# FTPLUS_v1_1.net
KiCad netlist of a schematic drawn in EasyEDA
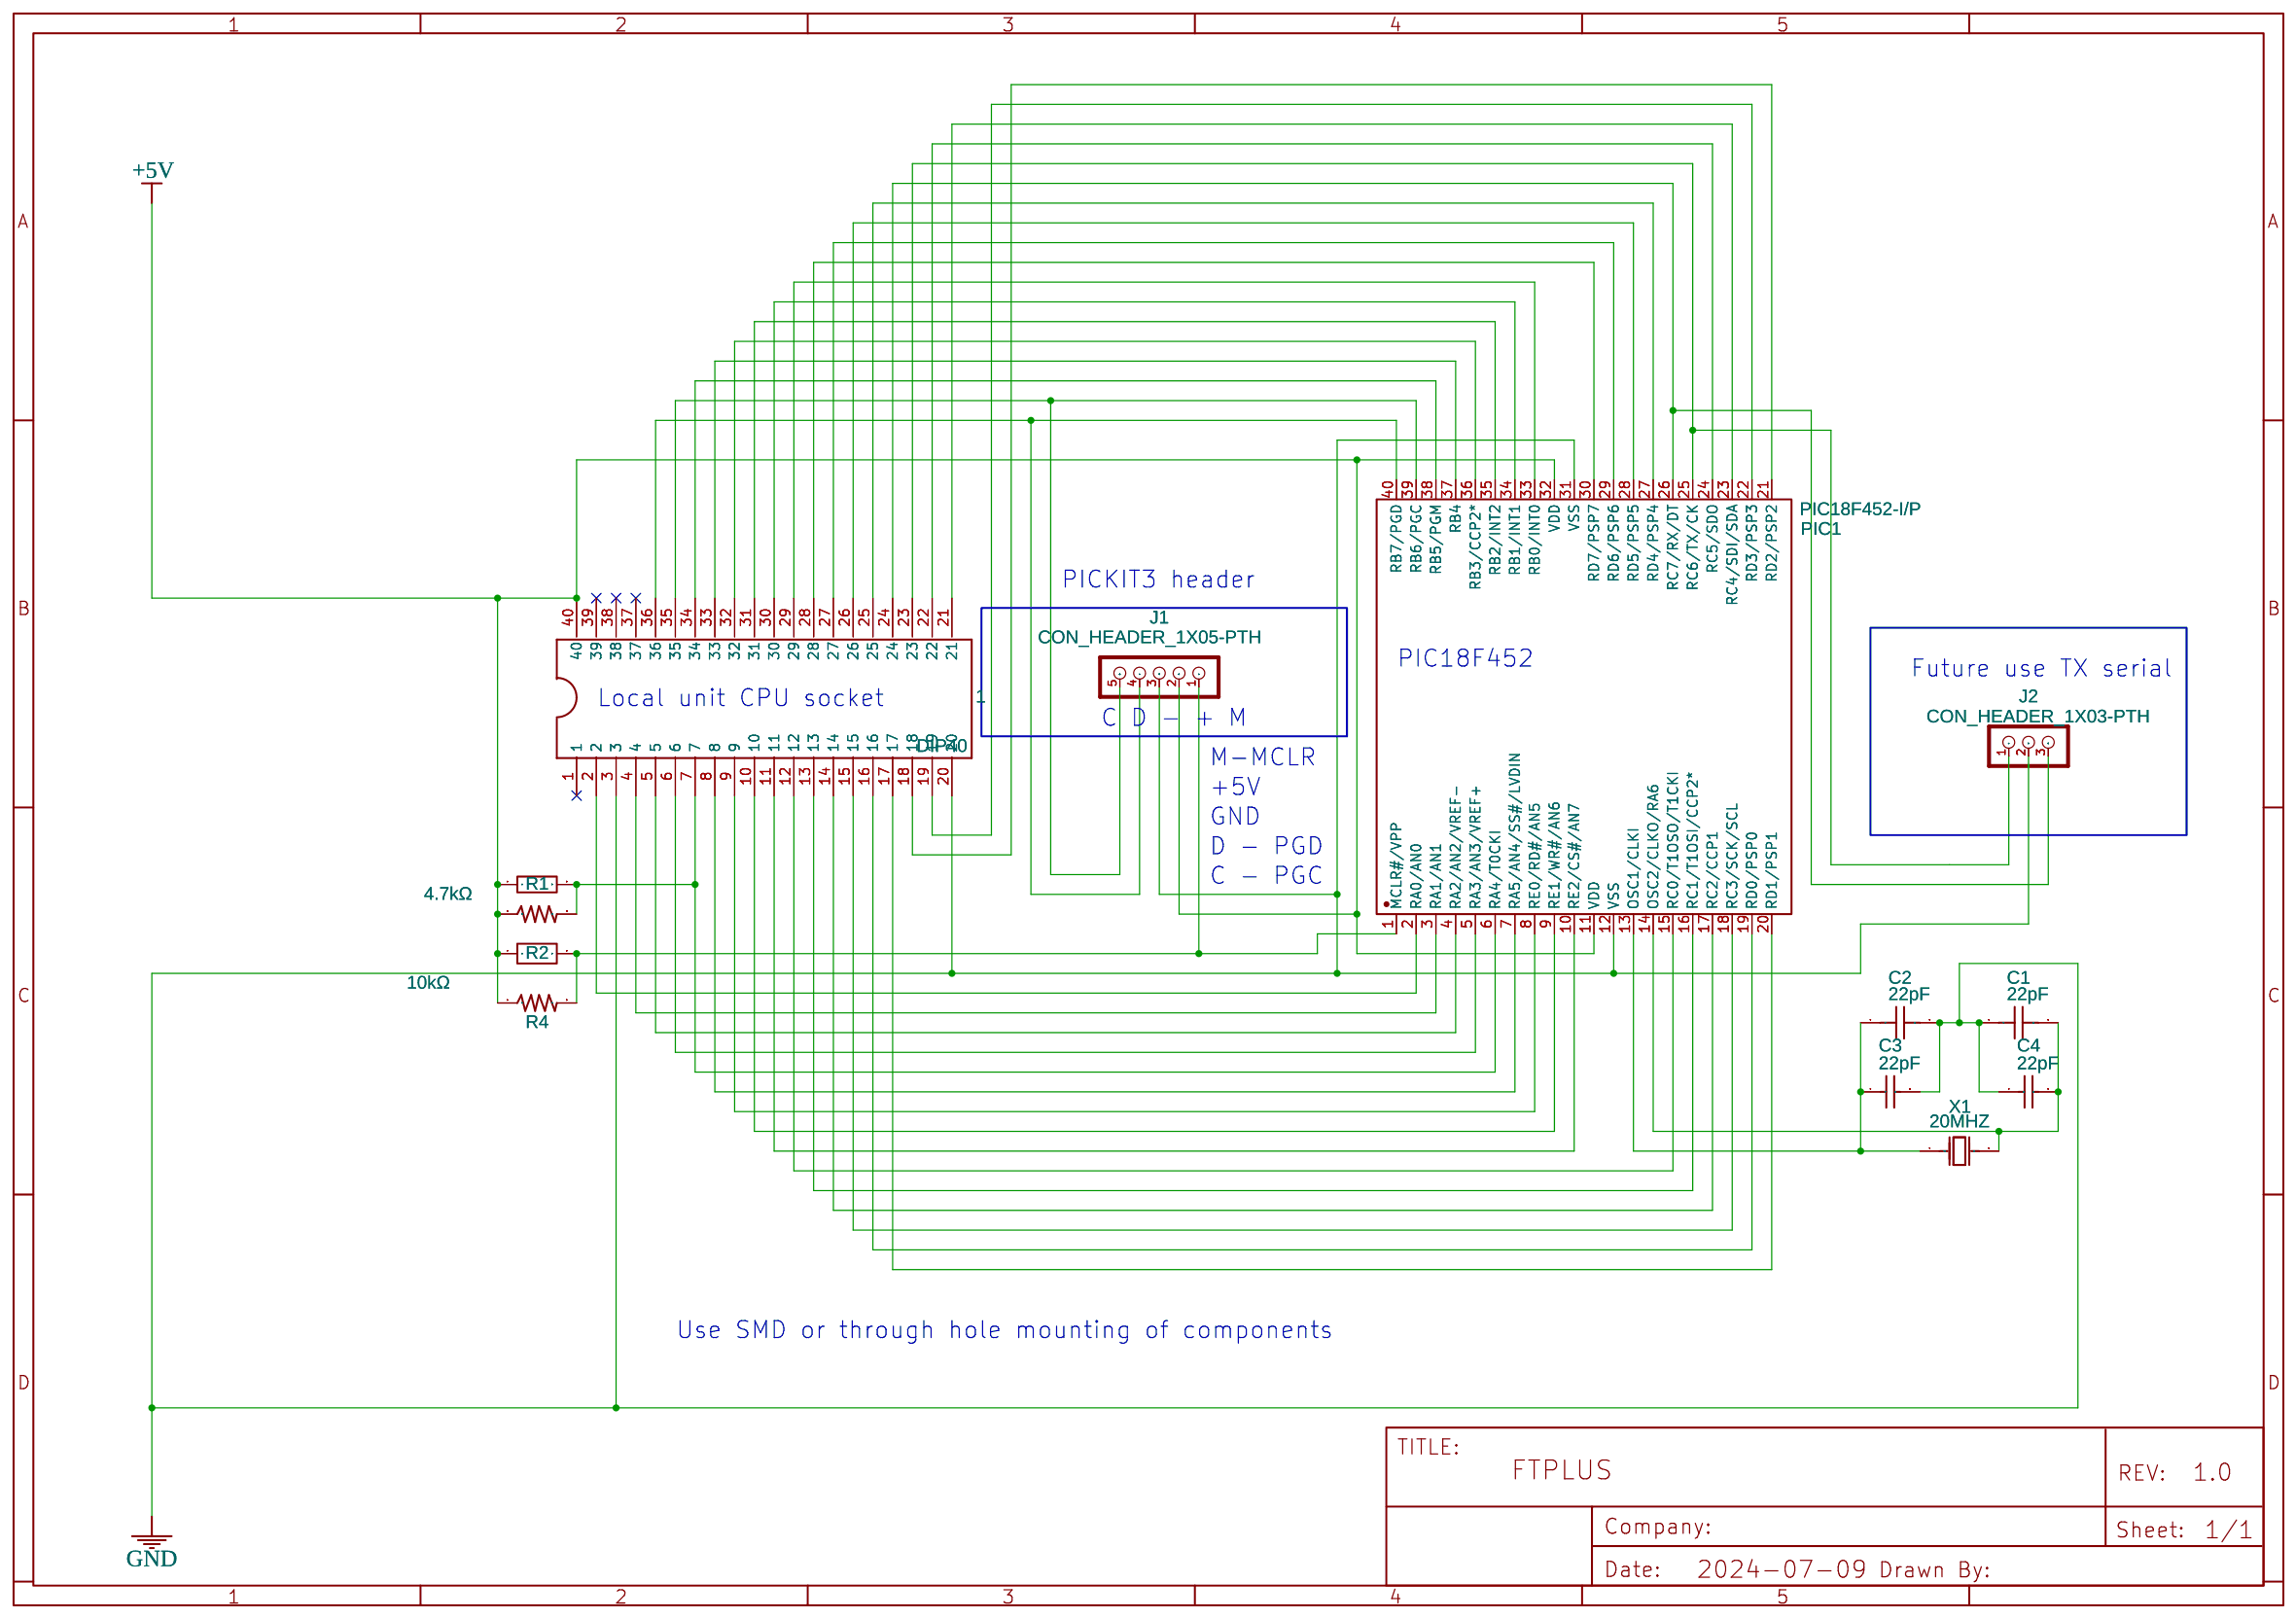
[diagram p0: schematic sheet]

(export (version "E")
  (design (tool "Eeschema 10.0.6"))
  (components
    (comp (ref "1") (value "DIP40") (libsource (lib "") (part "DIP40")))
    (comp (ref "C1")
      (value "22pF")
      (fields
        (field (name "Manufacturer Part") "CSA0603C0G220J500JT")
        (field (name "Manufacturer") "HRE(芯声)")
      )
      (libsource (lib "") (part "CSA0603C0G220J500JT"))
    )
    (comp (ref "C2")
      (value "22pF")
      (fields
        (field (name "Manufacturer Part") "CSA0603C0G220J500JT")
        (field (name "Manufacturer") "HRE(芯声)")
      )
      (libsource (lib "") (part "CSA0603C0G220J500JT"))
    )
    (comp (ref "C3")
      (value "22pF")
      (fields (field (name "Manufacturer Part") "22K-50V") (field (name "Manufacturer") "LCSC"))
      (libsource (lib "") (part "22pF"))
    )
    (comp (ref "C4")
      (value "22pF")
      (fields (field (name "Manufacturer Part") "22K-50V") (field (name "Manufacturer") "LCSC"))
      (libsource (lib "") (part "22pF"))
    )
    (comp (ref "J1") (value "CON_HEADER_1X05-PTH") (libsource (lib "") (part "CON_HEADER_1X05-PTH")))
    (comp (ref "J2") (value "CON_HEADER_1X03-PTH") (libsource (lib "") (part "CON_HEADER_1X03-PTH")))
    (comp (ref "PIC1")
      (value "PIC18F452-I/P")
      (fields (field (name "Manufacturer") "MICROCHIP(美国微芯)"))
      (libsource (lib "") (part "PIC18F452-I/P"))
    )
    (comp (ref "R1")
      (value "4.7kΩ")
      (fields
        (field (name "Manufacturer Part") "0603WAF4701T5E")
        (field (name "Manufacturer") "UNI-ROYAL(厚声)")
      )
      (libsource (lib "") (part "0603WAF4701T5E"))
    )
    (comp (ref "R2")
      (value "10kΩ")
      (fields
        (field (name "Manufacturer Part") "TC0325D1002T5F")
        (field (name "Manufacturer") "UNI-ROYAL(厚声)")
      )
      (libsource (lib "") (part "TC0325D1002T5F"))
    )
    (comp (ref "R3") (value "RESISTOR") (libsource (lib "") (part "RESISTOREZ")))
    (comp (ref "R4") (value "RESISTOREZ") (libsource (lib "") (part "RESISTOREZ")))
    (comp (ref "X1")
      (value "20MHZ")
      (fields (field (name "Manufacturer Part") "X49SD20MPB2SC") (field (name "Manufacturer") "EasyEDA"))
      (libsource (lib "") (part "20MHZ"))
    )
  )
  (nets
    (net (code "1") (name "+5V") (class "Default")
      (node (ref "1") (pin "40") (pinfunction "40_40") (pintype "bidirectional"))
      (node (ref "J1") (pin "2") (pinfunction "2_2") (pintype "unspecified"))
      (node (ref "PIC1") (pin "11") (pinfunction "VDD_11") (pintype "unspecified"))
      (node (ref "PIC1") (pin "32") (pinfunction "VDD_32") (pintype "unspecified"))
      (node (ref "R1") (pin "1") (pinfunction "1_1") (pintype "input"))
      (node (ref "R2") (pin "1") (pinfunction "1_1") (pintype "unspecified"))
      (node (ref "R3") (pin "1") (pinfunction "1_1") (pintype "unspecified"))
      (node (ref "R4") (pin "1") (pinfunction "1_1") (pintype "unspecified"))
    )
    (net (code "2") (name "GND") (class "Default")
      (node (ref "1") (pin "20") (pinfunction "20_20") (pintype "bidirectional"))
      (node (ref "1") (pin "3") (pinfunction "3_3") (pintype "bidirectional"))
      (node (ref "C1") (pin "1") (pinfunction "1_1") (pintype "unspecified"))
      (node (ref "C2") (pin "2") (pinfunction "2_2") (pintype "unspecified"))
      (node (ref "C3") (pin "2") (pinfunction "2_2") (pintype "input"))
      (node (ref "C4") (pin "1") (pinfunction "1_1") (pintype "input"))
      (node (ref "J1") (pin "3") (pinfunction "3_3") (pintype "unspecified"))
      (node (ref "J2") (pin "2") (pinfunction "2_2") (pintype "unspecified"))
      (node (ref "PIC1") (pin "12") (pinfunction "VSS_12") (pintype "unspecified"))
      (node (ref "PIC1") (pin "31") (pinfunction "VSS_31") (pintype "unspecified"))
    )
    (net (code "3") (name "Net-(PIC1-MCLR#{slash}VPP)") (class "Default")
      (node (ref "J1") (pin "1") (pinfunction "1_1") (pintype "unspecified"))
      (node (ref "PIC1") (pin "1") (pinfunction "MCLR#/VPP_1") (pintype "unspecified"))
      (node (ref "R2") (pin "2") (pinfunction "2_2") (pintype "unspecified"))
      (node (ref "R4") (pin "2") (pinfunction "2_2") (pintype "unspecified"))
    )
    (net (code "4") (name "Net-(PIC1-OSC1{slash}CLKI)") (class "Default")
      (node (ref "C2") (pin "1") (pinfunction "1_1") (pintype "unspecified"))
      (node (ref "C3") (pin "1") (pinfunction "1_1") (pintype "input"))
      (node (ref "PIC1") (pin "13") (pinfunction "OSC1/CLKI_13") (pintype "unspecified"))
      (node (ref "X1") (pin "1") (pinfunction "OSC1_1") (pintype "unspecified"))
    )
    (net (code "5") (name "Net-(PIC1-OSC2{slash}CLKO{slash}RA6)") (class "Default")
      (node (ref "C1") (pin "2") (pinfunction "2_2") (pintype "unspecified"))
      (node (ref "C4") (pin "2") (pinfunction "2_2") (pintype "input"))
      (node (ref "PIC1") (pin "14") (pinfunction "OSC2/CLKO/RA6_14") (pintype "unspecified"))
      (node (ref "X1") (pin "2") (pinfunction "OSC2_2") (pintype "unspecified"))
    )
    (net (code "6") (name "Net-(PIC1-RA0{slash}AN0)") (class "Default")
      (node (ref "1") (pin "2") (pinfunction "2_2") (pintype "bidirectional"))
      (node (ref "PIC1") (pin "2") (pinfunction "RA0/AN0_2") (pintype "unspecified"))
    )
    (net (code "7") (name "Net-(PIC1-RA1{slash}AN1)") (class "Default")
      (node (ref "1") (pin "4") (pinfunction "4_4") (pintype "bidirectional"))
      (node (ref "PIC1") (pin "3") (pinfunction "RA1/AN1_3") (pintype "unspecified"))
    )
    (net (code "8") (name "Net-(PIC1-RA2{slash}AN2{slash}VREF-)") (class "Default")
      (node (ref "1") (pin "5") (pinfunction "5_5") (pintype "bidirectional"))
      (node (ref "PIC1") (pin "4") (pinfunction "RA2/AN2/VREF-_4") (pintype "unspecified"))
    )
    (net (code "9") (name "Net-(PIC1-RA3{slash}AN3{slash}VREF+)") (class "Default")
      (node (ref "1") (pin "6") (pinfunction "6_6") (pintype "bidirectional"))
      (node (ref "PIC1") (pin "5") (pinfunction "RA3/AN3/VREF+_5") (pintype "unspecified"))
    )
    (net (code "10") (name "Net-(PIC1-RA4{slash}T0CKI)") (class "Default")
      (node (ref "1") (pin "7") (pinfunction "7_7") (pintype "bidirectional"))
      (node (ref "PIC1") (pin "6") (pinfunction "RA4/T0CKI_6") (pintype "unspecified"))
      (node (ref "R1") (pin "2") (pinfunction "2_2") (pintype "input"))
      (node (ref "R3") (pin "2") (pinfunction "2_2") (pintype "unspecified"))
    )
    (net (code "11") (name "Net-(PIC1-RA5{slash}AN4{slash}SS#{slash}LVDIN)") (class "Default")
      (node (ref "1") (pin "8") (pinfunction "8_8") (pintype "bidirectional"))
      (node (ref "PIC1") (pin "7") (pinfunction "RA5/AN4/SS#/LVDIN_7") (pintype "unspecified"))
    )
    (net (code "12") (name "Net-(PIC1-RB0{slash}INT0)") (class "Default")
      (node (ref "1") (pin "29") (pinfunction "29_29") (pintype "bidirectional"))
      (node (ref "PIC1") (pin "33") (pinfunction "RB0/INT0_33") (pintype "unspecified"))
    )
    (net (code "13") (name "Net-(PIC1-RB1{slash}INT1)") (class "Default")
      (node (ref "1") (pin "30") (pinfunction "30_30") (pintype "bidirectional"))
      (node (ref "PIC1") (pin "34") (pinfunction "RB1/INT1_34") (pintype "unspecified"))
    )
    (net (code "14") (name "Net-(PIC1-RB2{slash}INT2)") (class "Default")
      (node (ref "1") (pin "31") (pinfunction "31_31") (pintype "bidirectional"))
      (node (ref "PIC1") (pin "35") (pinfunction "RB2/INT2_35") (pintype "unspecified"))
    )
    (net (code "15") (name "Net-(PIC1-RB3{slash}CCP2*)") (class "Default")
      (node (ref "1") (pin "32") (pinfunction "32_32") (pintype "bidirectional"))
      (node (ref "PIC1") (pin "36") (pinfunction "RB3/CCP2*_36") (pintype "unspecified"))
    )
    (net (code "16") (name "Net-(PIC1-RB4)") (class "Default")
      (node (ref "1") (pin "33") (pinfunction "33_33") (pintype "bidirectional"))
      (node (ref "PIC1") (pin "37") (pinfunction "RB4_37") (pintype "unspecified"))
    )
    (net (code "17") (name "Net-(PIC1-RB5{slash}PGM)") (class "Default")
      (node (ref "1") (pin "34") (pinfunction "34_34") (pintype "bidirectional"))
      (node (ref "PIC1") (pin "38") (pinfunction "RB5/PGM_38") (pintype "unspecified"))
    )
    (net (code "18") (name "Net-(PIC1-RB6{slash}PGC)") (class "Default")
      (node (ref "1") (pin "35") (pinfunction "35_35") (pintype "bidirectional"))
      (node (ref "J1") (pin "5") (pinfunction "5_5") (pintype "unspecified"))
      (node (ref "PIC1") (pin "39") (pinfunction "RB6/PGC_39") (pintype "unspecified"))
    )
    (net (code "19") (name "Net-(PIC1-RB7{slash}PGD)") (class "Default")
      (node (ref "1") (pin "36") (pinfunction "36_36") (pintype "bidirectional"))
      (node (ref "J1") (pin "4") (pinfunction "4_4") (pintype "unspecified"))
      (node (ref "PIC1") (pin "40") (pinfunction "RB7/PGD_40") (pintype "unspecified"))
    )
    (net (code "20") (name "Net-(PIC1-RC0{slash}T1OSO{slash}T1CKI)") (class "Default")
      (node (ref "1") (pin "12") (pinfunction "12_12") (pintype "bidirectional"))
      (node (ref "PIC1") (pin "15") (pinfunction "RC0/T1OSO/T1CKI_15") (pintype "unspecified"))
    )
    (net (code "21") (name "Net-(PIC1-RC1{slash}T1OSI{slash}CCP2*)") (class "Default")
      (node (ref "1") (pin "13") (pinfunction "13_13") (pintype "bidirectional"))
      (node (ref "PIC1") (pin "16") (pinfunction "RC1/T1OSI/CCP2*_16") (pintype "unspecified"))
    )
    (net (code "22") (name "Net-(PIC1-RC2{slash}CCP1)") (class "Default")
      (node (ref "1") (pin "14") (pinfunction "14_14") (pintype "bidirectional"))
      (node (ref "PIC1") (pin "17") (pinfunction "RC2/CCP1_17") (pintype "unspecified"))
    )
    (net (code "23") (name "Net-(PIC1-RC3{slash}SCK{slash}SCL)") (class "Default")
      (node (ref "1") (pin "15") (pinfunction "15_15") (pintype "bidirectional"))
      (node (ref "PIC1") (pin "18") (pinfunction "RC3/SCK/SCL_18") (pintype "unspecified"))
    )
    (net (code "24") (name "Net-(PIC1-RC4{slash}SDI{slash}SDA)") (class "Default")
      (node (ref "1") (pin "21") (pinfunction "21_21") (pintype "bidirectional"))
      (node (ref "PIC1") (pin "23") (pinfunction "RC4/SDI/SDA_23") (pintype "unspecified"))
    )
    (net (code "25") (name "Net-(PIC1-RC5{slash}SDO)") (class "Default")
      (node (ref "1") (pin "22") (pinfunction "22_22") (pintype "bidirectional"))
      (node (ref "PIC1") (pin "24") (pinfunction "RC5/SDO_24") (pintype "unspecified"))
    )
    (net (code "26") (name "Net-(PIC1-RC6{slash}TX{slash}CK)") (class "Default")
      (node (ref "1") (pin "23") (pinfunction "23_23") (pintype "bidirectional"))
      (node (ref "J2") (pin "1") (pinfunction "1_1") (pintype "unspecified"))
      (node (ref "PIC1") (pin "25") (pinfunction "RC6/TX/CK_25") (pintype "unspecified"))
    )
    (net (code "27") (name "Net-(PIC1-RC7{slash}RX{slash}DT)") (class "Default")
      (node (ref "1") (pin "24") (pinfunction "24_24") (pintype "bidirectional"))
      (node (ref "J2") (pin "3") (pinfunction "3_3") (pintype "unspecified"))
      (node (ref "PIC1") (pin "26") (pinfunction "RC7/RX/DT_26") (pintype "unspecified"))
    )
    (net (code "28") (name "Net-(PIC1-RD0{slash}PSP0)") (class "Default")
      (node (ref "1") (pin "16") (pinfunction "16_16") (pintype "bidirectional"))
      (node (ref "PIC1") (pin "19") (pinfunction "RD0/PSP0_19") (pintype "unspecified"))
    )
    (net (code "29") (name "Net-(PIC1-RD1{slash}PSP1)") (class "Default")
      (node (ref "1") (pin "17") (pinfunction "17_17") (pintype "bidirectional"))
      (node (ref "PIC1") (pin "20") (pinfunction "RD1/PSP1_20") (pintype "unspecified"))
    )
    (net (code "30") (name "Net-(PIC1-RD2{slash}PSP2)") (class "Default")
      (node (ref "1") (pin "18") (pinfunction "18_18") (pintype "bidirectional"))
      (node (ref "PIC1") (pin "21") (pinfunction "RD2/PSP2_21") (pintype "unspecified"))
    )
    (net (code "31") (name "Net-(PIC1-RD3{slash}PSP3)") (class "Default")
      (node (ref "1") (pin "19") (pinfunction "19_19") (pintype "bidirectional"))
      (node (ref "PIC1") (pin "22") (pinfunction "RD3/PSP3_22") (pintype "unspecified"))
    )
    (net (code "32") (name "Net-(PIC1-RD4{slash}PSP4)") (class "Default")
      (node (ref "1") (pin "25") (pinfunction "25_25") (pintype "bidirectional"))
      (node (ref "PIC1") (pin "27") (pinfunction "RD4/PSP4_27") (pintype "unspecified"))
    )
    (net (code "33") (name "Net-(PIC1-RD5{slash}PSP5)") (class "Default")
      (node (ref "1") (pin "26") (pinfunction "26_26") (pintype "bidirectional"))
      (node (ref "PIC1") (pin "28") (pinfunction "RD5/PSP5_28") (pintype "unspecified"))
    )
    (net (code "34") (name "Net-(PIC1-RD6{slash}PSP6)") (class "Default")
      (node (ref "1") (pin "27") (pinfunction "27_27") (pintype "bidirectional"))
      (node (ref "PIC1") (pin "29") (pinfunction "RD6/PSP6_29") (pintype "unspecified"))
    )
    (net (code "35") (name "Net-(PIC1-RD7{slash}PSP7)") (class "Default")
      (node (ref "1") (pin "28") (pinfunction "28_28") (pintype "bidirectional"))
      (node (ref "PIC1") (pin "30") (pinfunction "RD7/PSP7_30") (pintype "unspecified"))
    )
    (net (code "36") (name "Net-(PIC1-RE0{slash}RD#{slash}AN5)") (class "Default")
      (node (ref "1") (pin "9") (pinfunction "9_9") (pintype "bidirectional"))
      (node (ref "PIC1") (pin "8") (pinfunction "RE0/RD#/AN5_8") (pintype "unspecified"))
    )
    (net (code "37") (name "Net-(PIC1-RE1{slash}WR#{slash}AN6)") (class "Default")
      (node (ref "1") (pin "10") (pinfunction "10_10") (pintype "bidirectional"))
      (node (ref "PIC1") (pin "9") (pinfunction "RE1/WR#/AN6_9") (pintype "unspecified"))
    )
    (net (code "38") (name "Net-(PIC1-RE2{slash}CS#{slash}AN7)") (class "Default")
      (node (ref "1") (pin "11") (pinfunction "11_11") (pintype "bidirectional"))
      (node (ref "PIC1") (pin "10") (pinfunction "RE2/CS#/AN7_10") (pintype "unspecified"))
    )
    (net (code "39") (name "unconnected-(1-Pad1)") (class "Default")
      (node (ref "1") (pin "1") (pinfunction "1_1") (pintype "bidirectional+no_connect"))
    )
    (net (code "40") (name "unconnected-(1-Pad37)") (class "Default")
      (node (ref "1") (pin "37") (pinfunction "37_37") (pintype "bidirectional+no_connect"))
    )
    (net (code "41") (name "unconnected-(1-Pad38)") (class "Default")
      (node (ref "1") (pin "38") (pinfunction "38_38") (pintype "bidirectional+no_connect"))
    )
    (net (code "42") (name "unconnected-(1-Pad39)") (class "Default")
      (node (ref "1") (pin "39") (pinfunction "39_39") (pintype "bidirectional+no_connect"))
    )
  )
)
